# IsoIonV0_1.net
KiCad netlist of a schematic drawn in EAGLE
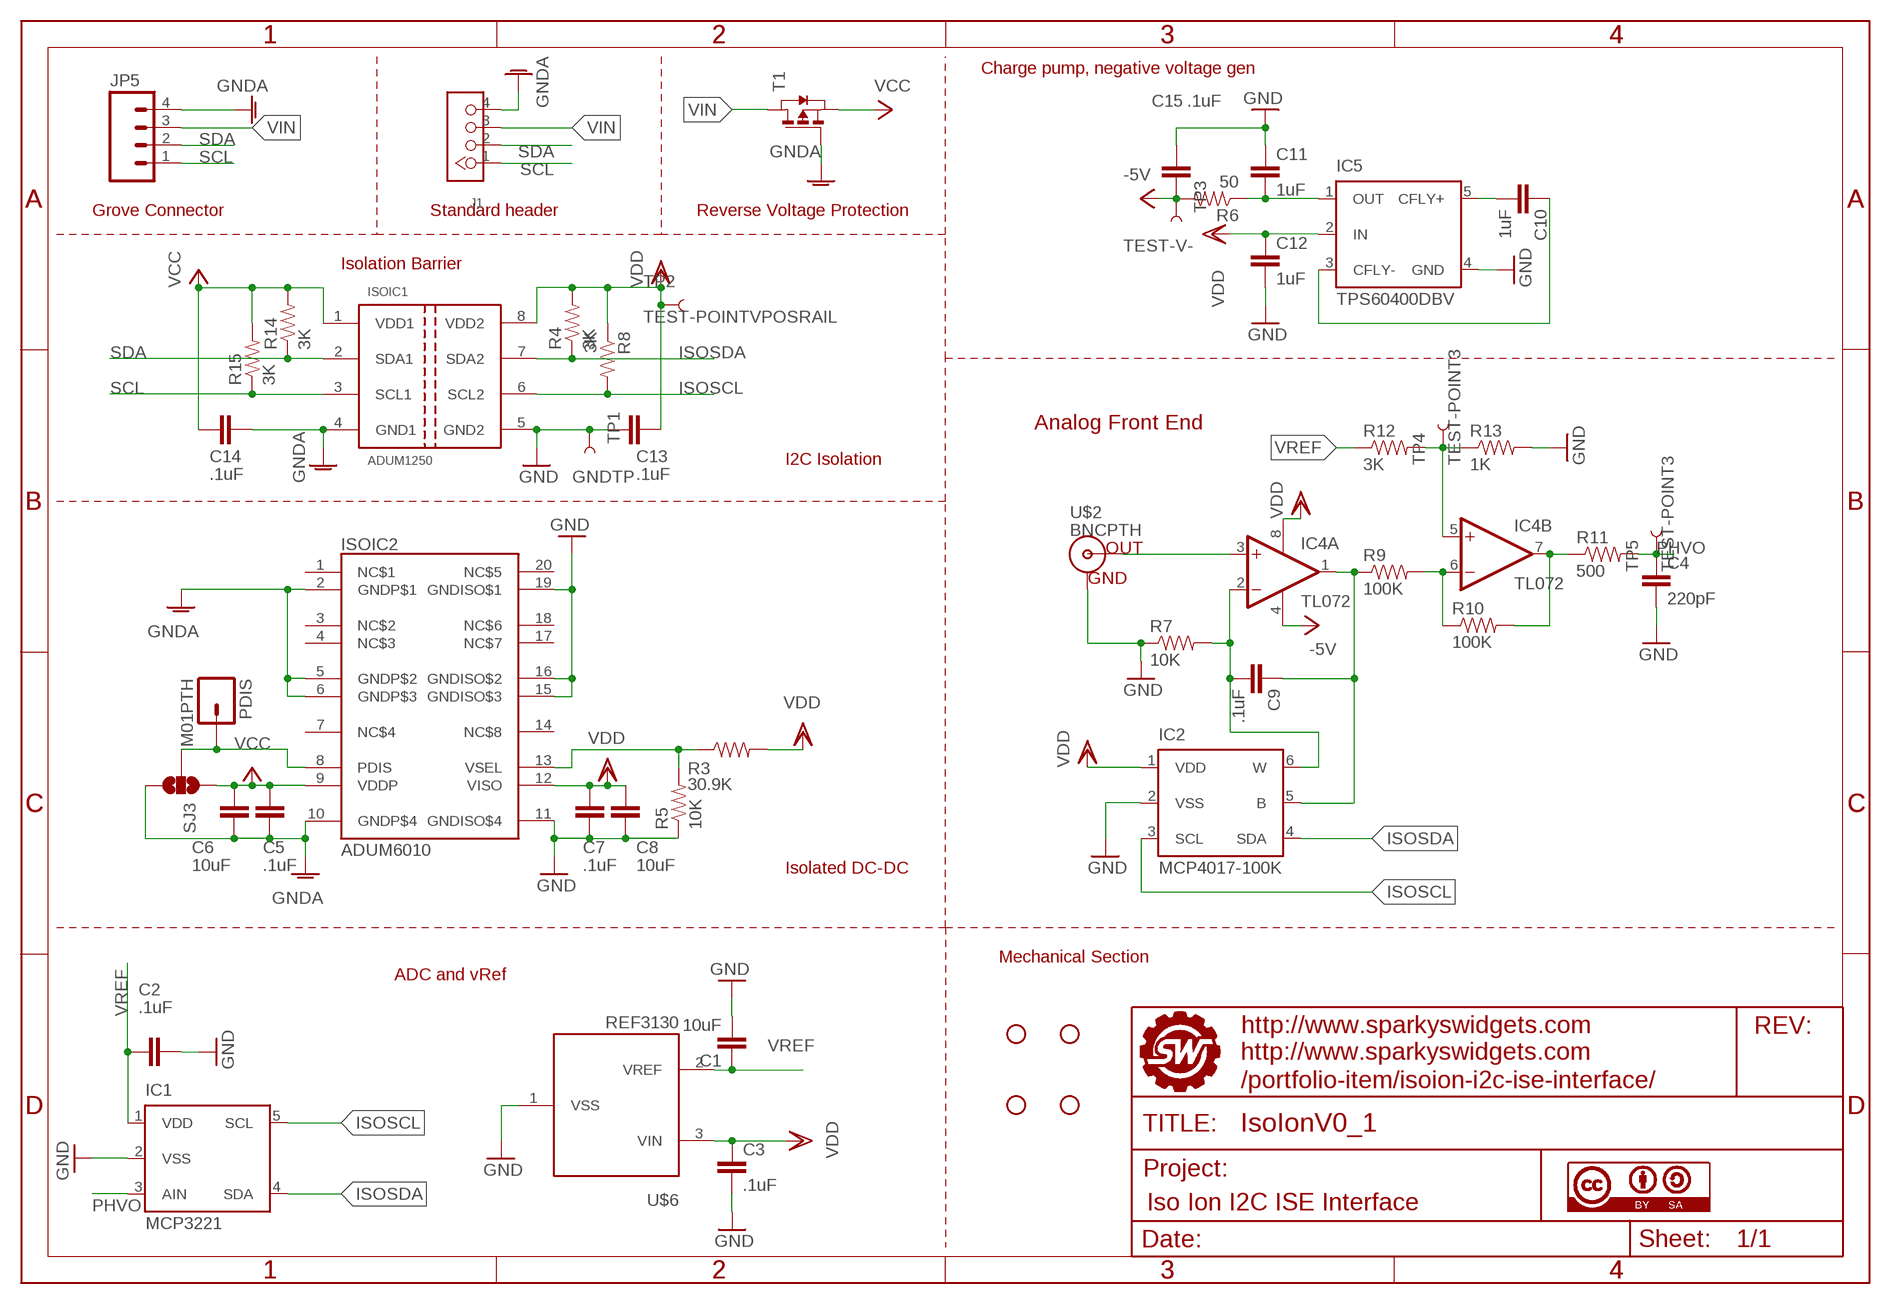
[diagram p0: schematic, sheet 1]

(export (version "E")
  (design (tool "Eeschema 10.0.6"))
  (components
    (comp (ref "C1")
      (value "10uF")
      (footprint "eagle-import:0805")
      (libsource (lib "eagle-import") (part "CAP0805"))
    )
    (comp (ref "C2")
      (value ".1uF")
      (footprint "eagle-import:0805")
      (libsource (lib "eagle-import") (part "CAP0805"))
    )
    (comp (ref "C3")
      (value ".1uF")
      (footprint "eagle-import:0805")
      (libsource (lib "eagle-import") (part "CAP0805"))
    )
    (comp (ref "C4")
      (value "220pF")
      (footprint "eagle-import:0805")
      (libsource (lib "eagle-import") (part "CAP0805"))
    )
    (comp (ref "C5")
      (value ".1uF")
      (footprint "eagle-import:0805")
      (libsource (lib "eagle-import") (part "CAP0805"))
    )
    (comp (ref "C6")
      (value "10uF")
      (footprint "eagle-import:0805")
      (libsource (lib "eagle-import") (part "CAP0805"))
    )
    (comp (ref "C7")
      (value ".1uF")
      (footprint "eagle-import:0805")
      (libsource (lib "eagle-import") (part "CAP0805"))
    )
    (comp (ref "C8")
      (value "10uF")
      (footprint "eagle-import:0805")
      (libsource (lib "eagle-import") (part "CAP0805"))
    )
    (comp (ref "C9")
      (value ".1uF")
      (footprint "eagle-import:0805")
      (libsource (lib "eagle-import") (part "CAP0805"))
    )
    (comp (ref "C10")
      (value "1uF")
      (footprint "eagle-import:0805")
      (libsource (lib "eagle-import") (part "CAP0805"))
    )
    (comp (ref "C11")
      (value "1uF")
      (footprint "eagle-import:0805")
      (libsource (lib "eagle-import") (part "CAP0805"))
    )
    (comp (ref "C12")
      (value "1uF")
      (footprint "eagle-import:0805")
      (libsource (lib "eagle-import") (part "CAP0805"))
    )
    (comp (ref "C13")
      (value ".1uF")
      (footprint "eagle-import:0805")
      (libsource (lib "eagle-import") (part "CAP0805"))
    )
    (comp (ref "C14")
      (value ".1uF")
      (footprint "eagle-import:0805")
      (libsource (lib "eagle-import") (part "CAP0805"))
    )
    (comp (ref "C15")
      (value ".1uF")
      (footprint "eagle-import:0805")
      (libsource (lib "eagle-import") (part "CAP0805"))
    )
    (comp (ref "IC1")
      (value "MCP3221")
      (footprint "eagle-import:SOT23-DBV")
      (libsource (lib "eagle-import") (part "MCP3221"))
    )
    (comp (ref "IC2")
      (value "MCP4017-100K")
      (footprint "eagle-import:SC70")
      (libsource (lib "eagle-import") (part "MCP4017"))
    )
    (comp (ref "IC4")
      (value "TL072")
      (footprint "eagle-import:SO08@1")
      (libsource (lib "eagle-import") (part "LM358D"))
    )
    (comp (ref "IC5")
      (value "TPS60400DBV")
      (footprint "eagle-import:SOT23-DBV")
      (libsource (lib "eagle-import") (part "TPS60400DBV"))
    )
    (comp (ref "ISOIC1")
      (value "ADUM1250")
      (footprint "eagle-import:SO08")
      (libsource (lib "eagle-import") (part "ADUM1250"))
    )
    (comp (ref "ISOIC2")
      (value "ADUM6010")
      (footprint "eagle-import:SSOP20")
      (libsource (lib "eagle-import") (part "ADUM6010"))
    )
    (comp (ref "J1")
      (value "TWIG-4P-2.0-2.0")
      (footprint "eagle-import:4P-2.0")
      (libsource (lib "eagle-import") (part "TWIG-4P-2.0-2.0"))
    )
    (comp (ref "JP1")
      (value "STAND-OFF")
      (footprint "eagle-import:STAND-OFF")
      (libsource (lib "eagle-import") (part "STAND-OFF"))
    )
    (comp (ref "JP2")
      (value "STAND-OFF")
      (footprint "eagle-import:STAND-OFF")
      (libsource (lib "eagle-import") (part "STAND-OFF"))
    )
    (comp (ref "JP3")
      (value "STAND-OFF")
      (footprint "eagle-import:STAND-OFF")
      (libsource (lib "eagle-import") (part "STAND-OFF"))
    )
    (comp (ref "JP4")
      (value "STAND-OFF")
      (footprint "eagle-import:STAND-OFF")
      (libsource (lib "eagle-import") (part "STAND-OFF"))
    )
    (comp (ref "JP5")
      (value "M04PTH")
      (footprint "eagle-import:1X04")
      (libsource (lib "eagle-import") (part "M04PTH"))
    )
    (comp (ref "PDIS")
      (value "M01PTH")
      (footprint "eagle-import:1X01")
      (libsource (lib "eagle-import") (part "M01PTH"))
    )
    (comp (ref "R3")
      (value "30.9K")
      (footprint "eagle-import:0805")
      (libsource (lib "eagle-import") (part "RESISTOR0805-RES"))
    )
    (comp (ref "R4")
      (value "3K")
      (footprint "eagle-import:0805")
      (libsource (lib "eagle-import") (part "RESISTOR0805-RES"))
    )
    (comp (ref "R5")
      (value "10K")
      (footprint "eagle-import:0805")
      (libsource (lib "eagle-import") (part "RESISTOR0805-RES"))
    )
    (comp (ref "R6")
      (value "50")
      (footprint "eagle-import:0805")
      (libsource (lib "eagle-import") (part "RESISTOR0805-RES"))
    )
    (comp (ref "R7")
      (value "10K")
      (footprint "eagle-import:0805")
      (libsource (lib "eagle-import") (part "RESISTOR0805-RES"))
    )
    (comp (ref "R8")
      (value "3K")
      (footprint "eagle-import:0805")
      (libsource (lib "eagle-import") (part "RESISTOR0805-RES"))
    )
    (comp (ref "R9")
      (value "100K")
      (footprint "eagle-import:0805")
      (libsource (lib "eagle-import") (part "RESISTOR0805-RES"))
    )
    (comp (ref "R10")
      (value "100K")
      (footprint "eagle-import:0805")
      (libsource (lib "eagle-import") (part "RESISTOR0805-RES"))
    )
    (comp (ref "R11")
      (value "500")
      (footprint "eagle-import:0805")
      (libsource (lib "eagle-import") (part "RESISTOR0805-RES"))
    )
    (comp (ref "R12")
      (value "3K")
      (footprint "eagle-import:0805")
      (libsource (lib "eagle-import") (part "RESISTOR0805-RES"))
    )
    (comp (ref "R13")
      (value "1K")
      (footprint "eagle-import:0805")
      (libsource (lib "eagle-import") (part "RESISTOR0805-RES"))
    )
    (comp (ref "R14")
      (value "3K")
      (footprint "eagle-import:0805")
      (libsource (lib "eagle-import") (part "RESISTOR0805-RES"))
    )
    (comp (ref "R15")
      (value "3K")
      (footprint "eagle-import:0805")
      (libsource (lib "eagle-import") (part "RESISTOR0805-RES"))
    )
    (comp (ref "SJ3")
      (value "SOLDERJUMPER_2WAYPASTE2&3")
      (footprint "eagle-import:SJ_3_PASTE2&3")
      (libsource (lib "eagle-import") (part "SOLDERJUMPER_2WAYPASTE2&3"))
    )
    (comp (ref "T1")
      (value "PMOSSOT23")
      (footprint "eagle-import:SOT-23")
      (libsource (lib "eagle-import") (part "PMOSSOT23"))
    )
    (comp (ref "TP1")
      (value "GNDTP")
      (footprint "eagle-import:TEST_GND")
      (libsource (lib "eagle-import") (part "TEST-POINTGND"))
    )
    (comp (ref "TP2")
      (value "TEST-POINTVPOSRAIL")
      (footprint "eagle-import:TEST_V+")
      (libsource (lib "eagle-import") (part "TEST-POINTVPOSRAIL"))
    )
    (comp (ref "TP3")
      (value "TEST-V-")
      (footprint "eagle-import:TEST_V-")
      (libsource (lib "eagle-import") (part "TEST-POINTNEGRAIL"))
    )
    (comp (ref "TP4")
      (value "TEST-POINT3")
      (footprint "eagle-import:PAD.03X.03")
      (libsource (lib "eagle-import") (part "TEST-POINT3"))
    )
    (comp (ref "TP5")
      (value "TEST-POINT3")
      (footprint "eagle-import:PAD.03X.03")
      (libsource (lib "eagle-import") (part "TEST-POINT3"))
    )
    (comp (ref "U$1")
      (value "FRAME_ISOION")
      (footprint "eagle-import:SWPCBLOGOWITHINFO")
      (libsource (lib "eagle-import") (part "FRAME_ISOION"))
    )
    (comp (ref "U$2")
      (value "BNCPTH")
      (footprint "eagle-import:BNC")
      (libsource (lib "eagle-import") (part "BNCPTH"))
    )
    (comp (ref "U$3")
      (value "CC-BY-SA")
      (footprint "eagle-import:CC-BY-SA")
      (libsource (lib "eagle-import") (part "CC-BY-SA"))
    )
    (comp (ref "U$6")
      (value "REF3130")
      (footprint "eagle-import:SOT-23")
      (libsource (lib "eagle-import") (part "MCP1541"))
    )
  )
  (nets
    (net (code "1") (name "-5V") (class "Default")
      (node (ref "C15") (pin "2") (pinfunction "2_2") (pintype "passive"))
      (node (ref "IC4") (pin "4") (pinfunction "V-_4") (pintype "power_in"))
      (node (ref "R6") (pin "2") (pinfunction "2_2") (pintype "passive"))
      (node (ref "TP3") (pin "P$1") (pinfunction "1_P$1") (pintype "bidirectional"))
    )
    (net (code "2") (name "/PHVO") (class "Default")
      (node (ref "C4") (pin "1") (pinfunction "1_1") (pintype "passive"))
      (node (ref "IC1") (pin "3") (pinfunction "AIN_3") (pintype "input"))
      (node (ref "R11") (pin "2") (pinfunction "2_2") (pintype "passive"))
      (node (ref "TP5") (pin "P$1") (pinfunction "1_P$1") (pintype "bidirectional"))
    )
    (net (code "3") (name "/SCL") (class "Default")
      (node (ref "ISOIC1") (pin "3") (pinfunction "SCL1_3") (pintype "bidirectional"))
      (node (ref "J1") (pin "1") (pinfunction "1_1") (pintype "bidirectional"))
      (node (ref "JP5") (pin "1") (pinfunction "1_1") (pintype "passive"))
      (node (ref "R15") (pin "1") (pinfunction "1_1") (pintype "passive"))
    )
    (net (code "4") (name "/SDA") (class "Default")
      (node (ref "ISOIC1") (pin "2") (pinfunction "SDA1_2") (pintype "bidirectional"))
      (node (ref "J1") (pin "2") (pinfunction "2_2") (pintype "bidirectional"))
      (node (ref "JP5") (pin "2") (pinfunction "2_2") (pintype "passive"))
      (node (ref "R14") (pin "1") (pinfunction "1_1") (pintype "passive"))
    )
    (net (code "5") (name "GND") (class "Default")
      (node (ref "C1") (pin "2") (pinfunction "2_2") (pintype "passive"))
      (node (ref "C11") (pin "1") (pinfunction "1_1") (pintype "passive"))
      (node (ref "C12") (pin "2") (pinfunction "2_2") (pintype "passive"))
      (node (ref "C13") (pin "1") (pinfunction "1_1") (pintype "passive"))
      (node (ref "C15") (pin "1") (pinfunction "1_1") (pintype "passive"))
      (node (ref "C2") (pin "1") (pinfunction "1_1") (pintype "passive"))
      (node (ref "C3") (pin "2") (pinfunction "2_2") (pintype "passive"))
      (node (ref "C4") (pin "2") (pinfunction "2_2") (pintype "passive"))
      (node (ref "C7") (pin "2") (pinfunction "2_2") (pintype "passive"))
      (node (ref "C8") (pin "2") (pinfunction "2_2") (pintype "passive"))
      (node (ref "IC1") (pin "2") (pinfunction "VSS_2") (pintype "power_in"))
      (node (ref "IC2") (pin "2") (pinfunction "VSS_2") (pintype "power_in"))
      (node (ref "IC5") (pin "4") (pinfunction "GND_4") (pintype "passive"))
      (node (ref "ISOIC1") (pin "5") (pinfunction "GND2_5") (pintype "power_in"))
      (node (ref "ISOIC2") (pin "11") (pinfunction "GNDISO$4_11") (pintype "power_in"))
      (node (ref "ISOIC2") (pin "15") (pinfunction "GNDISO$3_15") (pintype "power_in"))
      (node (ref "ISOIC2") (pin "16") (pinfunction "GNDISO$2_16") (pintype "power_in"))
      (node (ref "ISOIC2") (pin "19") (pinfunction "GNDISO$1_19") (pintype "power_in"))
      (node (ref "R13") (pin "2") (pinfunction "2_2") (pintype "passive"))
      (node (ref "R5") (pin "1") (pinfunction "1_1") (pintype "passive"))
      (node (ref "R7") (pin "1") (pinfunction "1_1") (pintype "passive"))
      (node (ref "TP1") (pin "P$1") (pinfunction "1_P$1") (pintype "bidirectional"))
      (node (ref "U$2") (pin "GND") (pinfunction "GND_GND") (pintype "bidirectional"))
      (node (ref "U$6") (pin "1") (pinfunction "VSS_1") (pintype "power_in"))
    )
    (net (code "6") (name "GNDA") (class "Default")
      (node (ref "C14") (pin "1") (pinfunction "1_1") (pintype "passive"))
      (node (ref "C5") (pin "2") (pinfunction "2_2") (pintype "passive"))
      (node (ref "C6") (pin "2") (pinfunction "2_2") (pintype "passive"))
      (node (ref "ISOIC1") (pin "4") (pinfunction "GND1_4") (pintype "power_in"))
      (node (ref "ISOIC2") (pin "10") (pinfunction "GNDP$4_10") (pintype "power_in"))
      (node (ref "ISOIC2") (pin "2") (pinfunction "GNDP$1_2") (pintype "power_in"))
      (node (ref "ISOIC2") (pin "5") (pinfunction "GNDP$2_5") (pintype "power_in"))
      (node (ref "ISOIC2") (pin "6") (pinfunction "GNDP$3_6") (pintype "power_in"))
      (node (ref "J1") (pin "4") (pinfunction "4_4") (pintype "bidirectional"))
      (node (ref "JP5") (pin "4") (pinfunction "4_4") (pintype "passive"))
      (node (ref "SJ3") (pin "3") (pinfunction "3_3") (pintype "passive"))
      (node (ref "T1") (pin "3") (pinfunction "G_3") (pintype "passive"))
    )
    (net (code "7") (name "ISOSCL") (class "Default")
      (node (ref "IC1") (pin "5") (pinfunction "SCL_5") (pintype "bidirectional"))
      (node (ref "IC2") (pin "3") (pinfunction "SCL_3") (pintype "bidirectional"))
      (node (ref "ISOIC1") (pin "6") (pinfunction "SCL2_6") (pintype "bidirectional"))
      (node (ref "R8") (pin "2") (pinfunction "2_2") (pintype "passive"))
    )
    (net (code "8") (name "ISOSDA") (class "Default")
      (node (ref "IC1") (pin "4") (pinfunction "SDA_4") (pintype "bidirectional"))
      (node (ref "IC2") (pin "4") (pinfunction "SDA_4") (pintype "bidirectional"))
      (node (ref "ISOIC1") (pin "7") (pinfunction "SDA2_7") (pintype "bidirectional"))
      (node (ref "R4") (pin "1") (pinfunction "1_1") (pintype "passive"))
    )
    (net (code "9") (name "Net-(IC2-B)") (class "Default")
      (node (ref "C9") (pin "1") (pinfunction "1_1") (pintype "passive"))
      (node (ref "IC2") (pin "5") (pinfunction "B_5") (pintype "power_in"))
      (node (ref "IC4") (pin "1") (pinfunction "OUT_1") (pintype "output"))
      (node (ref "R9") (pin "1") (pinfunction "1_1") (pintype "passive"))
    )
    (net (code "10") (name "Net-(IC2-W)") (class "Default")
      (node (ref "C9") (pin "2") (pinfunction "2_2") (pintype "passive"))
      (node (ref "IC2") (pin "6") (pinfunction "W_6") (pintype "bidirectional"))
      (node (ref "IC4") (pin "2") (pinfunction "-IN_2") (pintype "input"))
      (node (ref "R7") (pin "2") (pinfunction "2_2") (pintype "passive"))
    )
    (net (code "11") (name "Net-(IC4A-+IN)") (class "Default")
      (node (ref "IC4") (pin "3") (pinfunction "+IN_3") (pintype "input"))
      (node (ref "U$2") (pin "S") (pinfunction "OUT_S") (pintype "bidirectional"))
    )
    (net (code "12") (name "Net-(IC4B-+IN)") (class "Default")
      (node (ref "IC4") (pin "5") (pinfunction "+IN_5") (pintype "input"))
      (node (ref "R12") (pin "2") (pinfunction "2_2") (pintype "passive"))
      (node (ref "R13") (pin "1") (pinfunction "1_1") (pintype "passive"))
      (node (ref "TP4") (pin "P$1") (pinfunction "1_P$1") (pintype "bidirectional"))
    )
    (net (code "13") (name "Net-(IC4B--IN)") (class "Default")
      (node (ref "IC4") (pin "6") (pinfunction "-IN_6") (pintype "input"))
      (node (ref "R10") (pin "1") (pinfunction "1_1") (pintype "passive"))
      (node (ref "R9") (pin "2") (pinfunction "2_2") (pintype "passive"))
    )
    (net (code "14") (name "Net-(IC4B-OUT)") (class "Default")
      (node (ref "IC4") (pin "7") (pinfunction "OUT_7") (pintype "output"))
      (node (ref "R10") (pin "2") (pinfunction "2_2") (pintype "passive"))
      (node (ref "R11") (pin "1") (pinfunction "1_1") (pintype "passive"))
    )
    (net (code "15") (name "Net-(IC5-CFLY+)") (class "Default")
      (node (ref "C10") (pin "2") (pinfunction "2_2") (pintype "passive"))
      (node (ref "IC5") (pin "5") (pinfunction "CFLY+_5") (pintype "passive"))
    )
    (net (code "16") (name "Net-(IC5-CFLY-)") (class "Default")
      (node (ref "C10") (pin "1") (pinfunction "1_1") (pintype "passive"))
      (node (ref "IC5") (pin "3") (pinfunction "CFLY-_3") (pintype "power_in"))
    )
    (net (code "17") (name "Net-(IC5-OUT)") (class "Default")
      (node (ref "C11") (pin "2") (pinfunction "2_2") (pintype "passive"))
      (node (ref "IC5") (pin "1") (pinfunction "OUT_1") (pintype "input"))
      (node (ref "R6") (pin "1") (pinfunction "1_1") (pintype "passive"))
    )
    (net (code "18") (name "Net-(ISOIC2-PDIS)") (class "Default")
      (node (ref "ISOIC2") (pin "8") (pinfunction "PDIS_8") (pintype "input"))
      (node (ref "PDIS") (pin "1") (pinfunction "1_1") (pintype "passive"))
      (node (ref "SJ3") (pin "2") (pinfunction "2_2") (pintype "passive"))
    )
    (net (code "19") (name "Net-(ISOIC2-VSEL)") (class "Default")
      (node (ref "ISOIC2") (pin "13") (pinfunction "VSEL_13") (pintype "input"))
      (node (ref "R3") (pin "1") (pinfunction "1_1") (pintype "passive"))
      (node (ref "R5") (pin "2") (pinfunction "2_2") (pintype "passive"))
    )
    (net (code "20") (name "VCC") (class "Default")
      (node (ref "C14") (pin "2") (pinfunction "2_2") (pintype "passive"))
      (node (ref "C5") (pin "1") (pinfunction "1_1") (pintype "passive"))
      (node (ref "C6") (pin "1") (pinfunction "1_1") (pintype "passive"))
      (node (ref "ISOIC1") (pin "1") (pinfunction "VDD1_1") (pintype "power_in"))
      (node (ref "ISOIC2") (pin "9") (pinfunction "VDDP_9") (pintype "power_in"))
      (node (ref "R14") (pin "2") (pinfunction "2_2") (pintype "passive"))
      (node (ref "R15") (pin "2") (pinfunction "2_2") (pintype "passive"))
      (node (ref "SJ3") (pin "1") (pinfunction "1_1") (pintype "passive"))
      (node (ref "T1") (pin "2") (pinfunction "S_2") (pintype "passive"))
    )
    (net (code "21") (name "VDD") (class "Default")
      (node (ref "C12") (pin "1") (pinfunction "1_1") (pintype "passive"))
      (node (ref "C13") (pin "2") (pinfunction "2_2") (pintype "passive"))
      (node (ref "C3") (pin "1") (pinfunction "1_1") (pintype "passive"))
      (node (ref "C7") (pin "1") (pinfunction "1_1") (pintype "passive"))
      (node (ref "C8") (pin "1") (pinfunction "1_1") (pintype "passive"))
      (node (ref "IC2") (pin "1") (pinfunction "VDD_1") (pintype "bidirectional"))
      (node (ref "IC4") (pin "8") (pinfunction "V+_8") (pintype "power_in"))
      (node (ref "IC5") (pin "2") (pinfunction "IN_2") (pintype "input"))
      (node (ref "ISOIC1") (pin "8") (pinfunction "VDD2_8") (pintype "power_in"))
      (node (ref "ISOIC2") (pin "12") (pinfunction "VISO_12") (pintype "power_in"))
      (node (ref "R3") (pin "2") (pinfunction "2_2") (pintype "passive"))
      (node (ref "R4") (pin "2") (pinfunction "2_2") (pintype "passive"))
      (node (ref "R8") (pin "1") (pinfunction "1_1") (pintype "passive"))
      (node (ref "TP2") (pin "P$1") (pinfunction "1_P$1") (pintype "bidirectional"))
      (node (ref "U$6") (pin "3") (pinfunction "VIN_3") (pintype "power_in"))
    )
    (net (code "22") (name "VIN") (class "Default")
      (node (ref "J1") (pin "3") (pinfunction "3_3") (pintype "bidirectional"))
      (node (ref "JP5") (pin "3") (pinfunction "3_3") (pintype "passive"))
      (node (ref "T1") (pin "1") (pinfunction "D_1") (pintype "passive"))
    )
    (net (code "23") (name "VREF") (class "Default")
      (node (ref "C1") (pin "1") (pinfunction "1_1") (pintype "passive"))
      (node (ref "C2") (pin "2") (pinfunction "2_2") (pintype "passive"))
      (node (ref "IC1") (pin "1") (pinfunction "VDD_1") (pintype "power_in"))
      (node (ref "R12") (pin "1") (pinfunction "1_1") (pintype "passive"))
      (node (ref "U$6") (pin "2") (pinfunction "VREF_2") (pintype "output"))
    )
    (net (code "24") (name "unconnected-(ISOIC2-NC$1-Pad1)") (class "Default")
      (node (ref "ISOIC2") (pin "1") (pinfunction "NC$1_1") (pintype "no_connect"))
    )
    (net (code "25") (name "unconnected-(ISOIC2-NC$2-Pad3)") (class "Default")
      (node (ref "ISOIC2") (pin "3") (pinfunction "NC$2_3") (pintype "no_connect"))
    )
    (net (code "26") (name "unconnected-(ISOIC2-NC$3-Pad4)") (class "Default")
      (node (ref "ISOIC2") (pin "4") (pinfunction "NC$3_4") (pintype "no_connect"))
    )
    (net (code "27") (name "unconnected-(ISOIC2-NC$4-Pad7)") (class "Default")
      (node (ref "ISOIC2") (pin "7") (pinfunction "NC$4_7") (pintype "no_connect"))
    )
    (net (code "28") (name "unconnected-(ISOIC2-NC$5-Pad20)") (class "Default")
      (node (ref "ISOIC2") (pin "20") (pinfunction "NC$5_20") (pintype "no_connect"))
    )
    (net (code "29") (name "unconnected-(ISOIC2-NC$6-Pad18)") (class "Default")
      (node (ref "ISOIC2") (pin "18") (pinfunction "NC$6_18") (pintype "no_connect"))
    )
    (net (code "30") (name "unconnected-(ISOIC2-NC$7-Pad17)") (class "Default")
      (node (ref "ISOIC2") (pin "17") (pinfunction "NC$7_17") (pintype "no_connect"))
    )
    (net (code "31") (name "unconnected-(ISOIC2-NC$8-Pad14)") (class "Default")
      (node (ref "ISOIC2") (pin "14") (pinfunction "NC$8_14") (pintype "no_connect"))
    )
  )
)
